# Pegelwandlung.net
KiCad netlist of a schematic drawn in EAGLE
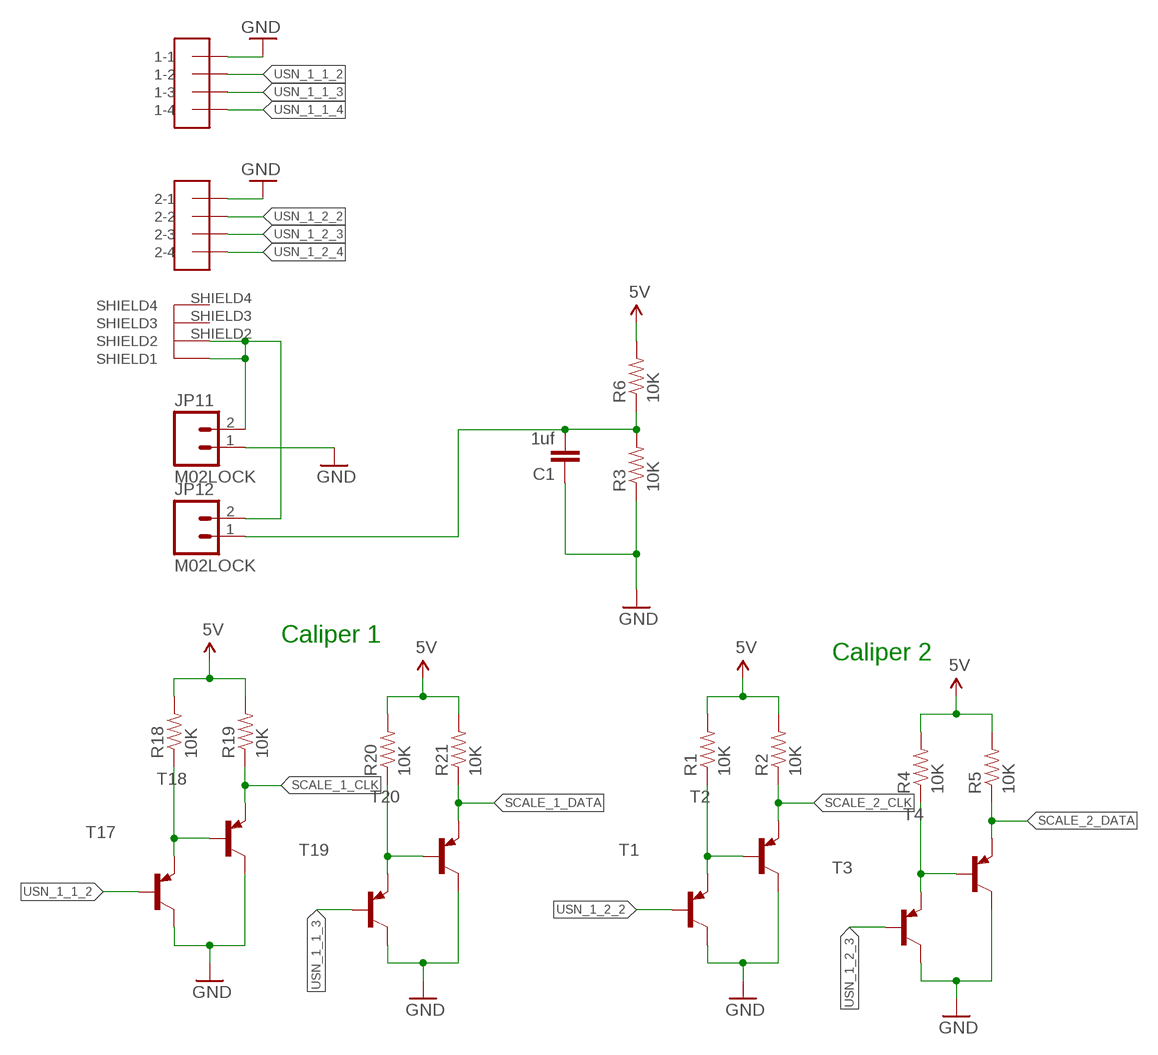
[diagram p0: schematic, sheet 1]

(export (version "E")
  (design (tool "Eeschema 10.0.6"))
  (components
    (comp (ref "C1")
      (value "1uf")
      (footprint "eagle-import:0805")
      (libsource (lib "eagle-import") (part "CAP0805"))
    )
    (comp (ref "JP11")
      (value "M02LOCK")
      (footprint "eagle-import:1X02_LOCK")
      (libsource (lib "eagle-import") (part "M02LOCK"))
    )
    (comp (ref "JP12")
      (value "M02LOCK")
      (footprint "eagle-import:1X02_LOCK")
      (libsource (lib "eagle-import") (part "M02LOCK"))
    )
    (comp (ref "R1")
      (value "10K")
      (footprint "eagle-import:0603-RES")
      (libsource (lib "eagle-import") (part "RESISTOR0603-RES"))
    )
    (comp (ref "R2")
      (value "10K")
      (footprint "eagle-import:0603-RES")
      (libsource (lib "eagle-import") (part "RESISTOR0603-RES"))
    )
    (comp (ref "R3")
      (value "10K")
      (footprint "eagle-import:0603-RES")
      (libsource (lib "eagle-import") (part "RESISTOR0603-RES"))
    )
    (comp (ref "R4")
      (value "10K")
      (footprint "eagle-import:0603-RES")
      (libsource (lib "eagle-import") (part "RESISTOR0603-RES"))
    )
    (comp (ref "R5")
      (value "10K")
      (footprint "eagle-import:0603-RES")
      (libsource (lib "eagle-import") (part "RESISTOR0603-RES"))
    )
    (comp (ref "R6")
      (value "10K")
      (footprint "eagle-import:0603-RES")
      (libsource (lib "eagle-import") (part "RESISTOR0603-RES"))
    )
    (comp (ref "R18")
      (value "10K")
      (footprint "eagle-import:0603-RES")
      (libsource (lib "eagle-import") (part "RESISTOR0603-RES"))
    )
    (comp (ref "R19")
      (value "10K")
      (footprint "eagle-import:0603-RES")
      (libsource (lib "eagle-import") (part "RESISTOR0603-RES"))
    )
    (comp (ref "R20")
      (value "10K")
      (footprint "eagle-import:0603-RES")
      (libsource (lib "eagle-import") (part "RESISTOR0603-RES"))
    )
    (comp (ref "R21")
      (value "10K")
      (footprint "eagle-import:0603-RES")
      (libsource (lib "eagle-import") (part "RESISTOR0603-RES"))
    )
    (comp (ref "T1")
      (value "-PNP-SOT23-BCE")
      (footprint "eagle-import:SOT23-BCE")
      (libsource (lib "eagle-import") (part "-PNP-SOT23-BCE"))
    )
    (comp (ref "T2")
      (value "-PNP-SOT23-BCE")
      (footprint "eagle-import:SOT23-BCE")
      (libsource (lib "eagle-import") (part "-PNP-SOT23-BCE"))
    )
    (comp (ref "T3")
      (value "-PNP-SOT23-BCE")
      (footprint "eagle-import:SOT23-BCE")
      (libsource (lib "eagle-import") (part "-PNP-SOT23-BCE"))
    )
    (comp (ref "T4")
      (value "-PNP-SOT23-BCE")
      (footprint "eagle-import:SOT23-BCE")
      (libsource (lib "eagle-import") (part "-PNP-SOT23-BCE"))
    )
    (comp (ref "T17")
      (value "-PNP-SOT23-BCE")
      (footprint "eagle-import:SOT23-BCE")
      (libsource (lib "eagle-import") (part "-PNP-SOT23-BCE"))
    )
    (comp (ref "T18")
      (value "-PNP-SOT23-BCE")
      (footprint "eagle-import:SOT23-BCE")
      (libsource (lib "eagle-import") (part "-PNP-SOT23-BCE"))
    )
    (comp (ref "T19")
      (value "-PNP-SOT23-BCE")
      (footprint "eagle-import:SOT23-BCE")
      (libsource (lib "eagle-import") (part "-PNP-SOT23-BCE"))
    )
    (comp (ref "T20")
      (value "-PNP-SOT23-BCE")
      (footprint "eagle-import:SOT23-BCE")
      (libsource (lib "eagle-import") (part "-PNP-SOT23-BCE"))
    )
    (comp (ref "U$7")
      (value "USB-A-2")
      (footprint "eagle-import:USB-A-2")
      (libsource (lib "eagle-import") (part "USB-A-2"))
    )
  )
  (nets
    (net (code "1") (name "5V") (class "Default")
      (node (ref "R1") (pin "2") (pinfunction "2_2") (pintype "passive"))
      (node (ref "R18") (pin "2") (pinfunction "2_2") (pintype "passive"))
      (node (ref "R19") (pin "2") (pinfunction "2_2") (pintype "passive"))
      (node (ref "R2") (pin "2") (pinfunction "2_2") (pintype "passive"))
      (node (ref "R20") (pin "2") (pinfunction "2_2") (pintype "passive"))
      (node (ref "R21") (pin "2") (pinfunction "2_2") (pintype "passive"))
      (node (ref "R4") (pin "2") (pinfunction "2_2") (pintype "passive"))
      (node (ref "R5") (pin "2") (pinfunction "2_2") (pintype "passive"))
      (node (ref "R6") (pin "2") (pinfunction "2_2") (pintype "passive"))
    )
    (net (code "2") (name "GND") (class "Default")
      (node (ref "C1") (pin "1") (pinfunction "1_1") (pintype "passive"))
      (node (ref "JP11") (pin "1") (pinfunction "1_1") (pintype "passive"))
      (node (ref "R3") (pin "1") (pinfunction "1_1") (pintype "passive"))
      (node (ref "T1") (pin "C") (pinfunction "C_C") (pintype "passive"))
      (node (ref "T17") (pin "C") (pinfunction "C_C") (pintype "passive"))
      (node (ref "T18") (pin "C") (pinfunction "C_C") (pintype "passive"))
      (node (ref "T19") (pin "C") (pinfunction "C_C") (pintype "passive"))
      (node (ref "T2") (pin "C") (pinfunction "C_C") (pintype "passive"))
      (node (ref "T20") (pin "C") (pinfunction "C_C") (pintype "passive"))
      (node (ref "T3") (pin "C") (pinfunction "C_C") (pintype "passive"))
      (node (ref "T4") (pin "C") (pinfunction "C_C") (pintype "passive"))
      (node (ref "U$7") (pin "1-1") (pinfunction "1-1_1-1") (pintype "bidirectional"))
      (node (ref "U$7") (pin "2-1") (pinfunction "2-1_2-1") (pintype "bidirectional"))
    )
    (net (code "3") (name "Net-(C1-Pad2)") (class "Default")
      (node (ref "C1") (pin "2") (pinfunction "2_2") (pintype "passive"))
      (node (ref "JP12") (pin "1") (pinfunction "1_1") (pintype "passive"))
      (node (ref "R3") (pin "2") (pinfunction "2_2") (pintype "passive"))
      (node (ref "R6") (pin "1") (pinfunction "1_1") (pintype "passive"))
    )
    (net (code "4") (name "Net-(JP11-Pad2)") (class "Default")
      (node (ref "JP11") (pin "2") (pinfunction "2_2") (pintype "passive"))
      (node (ref "JP12") (pin "2") (pinfunction "2_2") (pintype "passive"))
      (node (ref "U$7") (pin "SHIELD1") (pinfunction "SHIELD1_SHIELD1") (pintype "bidirectional"))
      (node (ref "U$7") (pin "SHIELD2") (pinfunction "SHIELD2_SHIELD2") (pintype "bidirectional"))
    )
    (net (code "5") (name "Net-(R1-Pad1)") (class "Default")
      (node (ref "R1") (pin "1") (pinfunction "1_1") (pintype "passive"))
      (node (ref "T1") (pin "E") (pinfunction "E_E") (pintype "passive"))
      (node (ref "T2") (pin "B") (pinfunction "B_B") (pintype "passive"))
    )
    (net (code "6") (name "Net-(R4-Pad1)") (class "Default")
      (node (ref "R4") (pin "1") (pinfunction "1_1") (pintype "passive"))
      (node (ref "T3") (pin "E") (pinfunction "E_E") (pintype "passive"))
      (node (ref "T4") (pin "B") (pinfunction "B_B") (pintype "passive"))
    )
    (net (code "7") (name "Net-(R18-Pad1)") (class "Default")
      (node (ref "R18") (pin "1") (pinfunction "1_1") (pintype "passive"))
      (node (ref "T17") (pin "E") (pinfunction "E_E") (pintype "passive"))
      (node (ref "T18") (pin "B") (pinfunction "B_B") (pintype "passive"))
    )
    (net (code "8") (name "Net-(R20-Pad1)") (class "Default")
      (node (ref "R20") (pin "1") (pinfunction "1_1") (pintype "passive"))
      (node (ref "T19") (pin "E") (pinfunction "E_E") (pintype "passive"))
      (node (ref "T20") (pin "B") (pinfunction "B_B") (pintype "passive"))
    )
    (net (code "9") (name "SCALE_1_CLK") (class "Default")
      (node (ref "R19") (pin "1") (pinfunction "1_1") (pintype "passive"))
      (node (ref "T18") (pin "E") (pinfunction "E_E") (pintype "passive"))
    )
    (net (code "10") (name "SCALE_1_DATA") (class "Default")
      (node (ref "R21") (pin "1") (pinfunction "1_1") (pintype "passive"))
      (node (ref "T20") (pin "E") (pinfunction "E_E") (pintype "passive"))
    )
    (net (code "11") (name "SCALE_2_CLK") (class "Default")
      (node (ref "R2") (pin "1") (pinfunction "1_1") (pintype "passive"))
      (node (ref "T2") (pin "E") (pinfunction "E_E") (pintype "passive"))
    )
    (net (code "12") (name "SCALE_2_DATA") (class "Default")
      (node (ref "R5") (pin "1") (pinfunction "1_1") (pintype "passive"))
      (node (ref "T4") (pin "E") (pinfunction "E_E") (pintype "passive"))
    )
    (net (code "13") (name "USN_1_1_2") (class "Default")
      (node (ref "T17") (pin "B") (pinfunction "B_B") (pintype "passive"))
      (node (ref "U$7") (pin "1-2") (pinfunction "1-2_1-2") (pintype "bidirectional"))
    )
    (net (code "14") (name "USN_1_1_3") (class "Default")
      (node (ref "T19") (pin "B") (pinfunction "B_B") (pintype "passive"))
      (node (ref "U$7") (pin "1-3") (pinfunction "1-3_1-3") (pintype "bidirectional"))
    )
    (net (code "15") (name "USN_1_1_4") (class "Default")
      (node (ref "U$7") (pin "1-4") (pinfunction "1-4_1-4") (pintype "bidirectional"))
    )
    (net (code "16") (name "USN_1_2_2") (class "Default")
      (node (ref "T1") (pin "B") (pinfunction "B_B") (pintype "passive"))
      (node (ref "U$7") (pin "2-2") (pinfunction "2-2_2-2") (pintype "bidirectional"))
    )
    (net (code "17") (name "USN_1_2_3") (class "Default")
      (node (ref "T3") (pin "B") (pinfunction "B_B") (pintype "passive"))
      (node (ref "U$7") (pin "2-3") (pinfunction "2-3_2-3") (pintype "bidirectional"))
    )
    (net (code "18") (name "USN_1_2_4") (class "Default")
      (node (ref "U$7") (pin "2-4") (pinfunction "2-4_2-4") (pintype "bidirectional"))
    )
    (net (code "19") (name "unconnected-(U$7-PadSHIELD3)") (class "Default")
      (node (ref "U$7") (pin "SHIELD3") (pinfunction "SHIELD3_SHIELD3") (pintype "bidirectional"))
    )
    (net (code "20") (name "unconnected-(U$7-PadSHIELD4)") (class "Default")
      (node (ref "U$7") (pin "SHIELD4") (pinfunction "SHIELD4_SHIELD4") (pintype "bidirectional"))
    )
  )
)
